# 1-Schematic_Task_10_1HD.net
KiCad netlist of a schematic drawn in EasyEDA
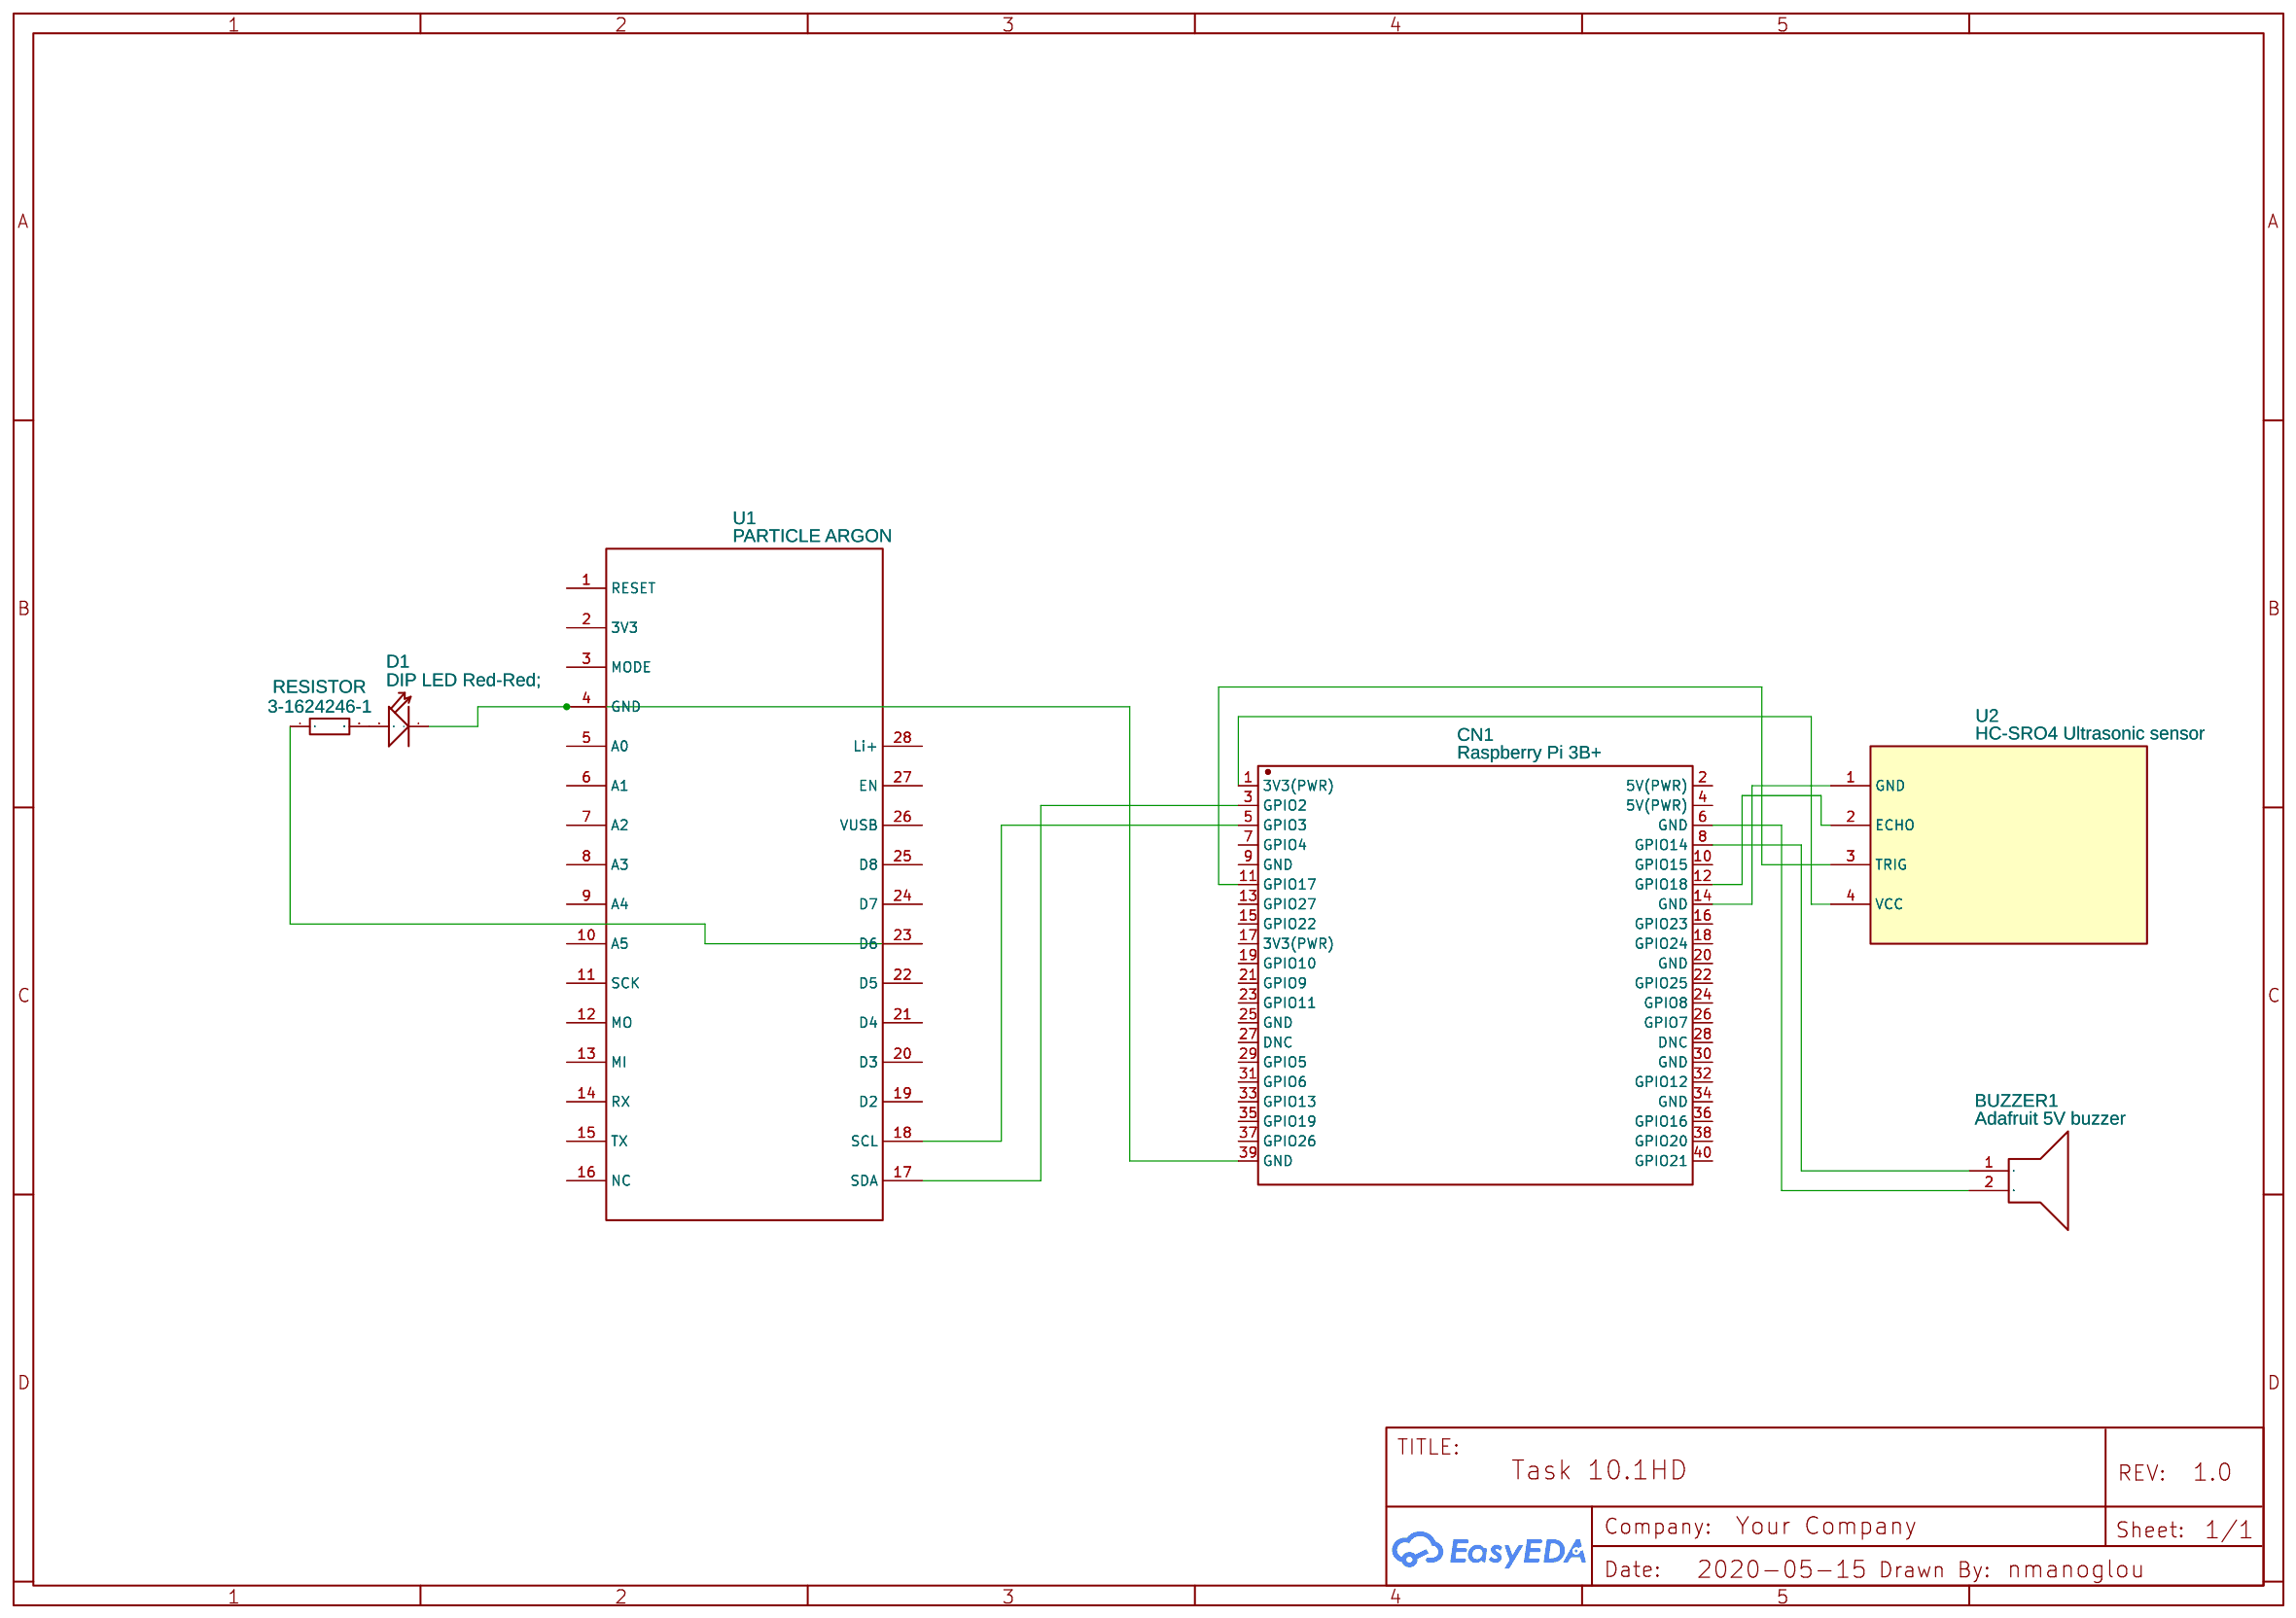
[diagram p0: schematic sheet]

(export (version "E")
  (design (tool "Eeschema 10.0.6"))
  (components
    (comp (ref "BUZZER1")
      (value "Adafruit 5V buzzer")
      (fields
        (field (name "BOM_Manufacturer Part") "GMC12085YA-16R2048")
        (field (name "BOM_Supplier Part") "C252920")
      )
      (libsource (lib "") (part "GMC12085YA-16R2048"))
    )
    (comp (ref "CN1") (value "Raspberry Pi 3B+") (libsource (lib "") (part "Raspberry Pi 2")))
    (comp (ref "D1")
      (value "DIP LED Red-Red;")
      (fields (field (name "BOM_Manufacturer Part") "?"))
      (libsource (lib "") (part "DIP LED Red-Red;"))
    )
    (comp (ref "RESISTOR")
      (value "3-1624246-1")
      (fields (field (name "BOM_Supplier Part") "C306238"))
      (libsource (lib "") (part "3-1624246-1"))
    )
    (comp (ref "U1") (value "PARTICLE ARGON") (libsource (lib "") (part "PARTICLE ARGON")))
    (comp (ref "U2")
      (value "HC-SRO4 Ultrasonic sensor")
      (libsource (lib "") (part "38 kHz modulated IR sensor"))
    )
  )
  (nets
    (net (code "1") (name "Net-(BUZZER1-Pad2)") (class "Default")
      (node (ref "BUZZER1") (pin "2") (pinfunction "2_2") (pintype "unspecified"))
      (node (ref "CN1") (pin "6") (pinfunction "GND_6") (pintype "passive"))
    )
    (net (code "2") (name "Net-(CN1-GPIO2)") (class "Default")
      (node (ref "CN1") (pin "3") (pinfunction "GPIO2_3") (pintype "bidirectional"))
      (node (ref "U1") (pin "17") (pinfunction "SDA_17") (pintype "unspecified"))
    )
    (net (code "3") (name "Net-(CN1-GPIO3)") (class "Default")
      (node (ref "CN1") (pin "5") (pinfunction "GPIO3_5") (pintype "bidirectional"))
      (node (ref "U1") (pin "18") (pinfunction "SCL_18") (pintype "unspecified"))
    )
    (net (code "4") (name "Net-(CN1-GPIO14)") (class "Default")
      (node (ref "BUZZER1") (pin "1") (pinfunction "1_1") (pintype "unspecified"))
      (node (ref "CN1") (pin "8") (pinfunction "GPIO14_8") (pintype "passive"))
    )
    (net (code "5") (name "Net-(CN1-GPIO17)") (class "Default")
      (node (ref "CN1") (pin "11") (pinfunction "GPIO17_11") (pintype "bidirectional"))
      (node (ref "U2") (pin "3") (pinfunction "TRIG_3") (pintype "unspecified"))
    )
    (net (code "6") (name "Net-(CN1-GPIO18)") (class "Default")
      (node (ref "CN1") (pin "12") (pinfunction "GPIO18_12") (pintype "bidirectional"))
      (node (ref "U2") (pin "2") (pinfunction "ECHO_2") (pintype "unspecified"))
    )
    (net (code "7") (name "Net-(D1-+)") (class "Default")
      (node (ref "D1") (pin "A") (pinfunction "+_A") (pintype "unspecified"))
      (node (ref "RESISTOR") (pin "2") (pinfunction "2_2") (pintype "unspecified"))
    )
    (net (code "8") (name "Net-(D1--)") (class "Default")
      (node (ref "CN1") (pin "39") (pinfunction "GND_39") (pintype "passive"))
      (node (ref "D1") (pin "K") (pinfunction "-_K") (pintype "unspecified"))
      (node (ref "U1") (pin "4") (pinfunction "GND_4") (pintype "unspecified"))
    )
    (net (code "9") (name "Net-(U1-D6)") (class "Default")
      (node (ref "RESISTOR") (pin "1") (pinfunction "1_1") (pintype "unspecified"))
      (node (ref "U1") (pin "23") (pinfunction "D6_23") (pintype "unspecified"))
    )
    (net (code "10") (name "Net-(U2-GND)") (class "Default")
      (node (ref "CN1") (pin "14") (pinfunction "GND_14") (pintype "passive"))
      (node (ref "U2") (pin "1") (pinfunction "GND_1") (pintype "unspecified"))
    )
    (net (code "11") (name "Net-(U2-VCC)") (class "Default")
      (node (ref "CN1") (pin "1") (pinfunction "3V3(PWR)_1") (pintype "passive"))
      (node (ref "U2") (pin "4") (pinfunction "VCC_4") (pintype "unspecified"))
    )
    (net (code "12") (name "unconnected-(CN1-3V3(PWR)-Pad17)") (class "Default")
      (node (ref "CN1") (pin "17") (pinfunction "3V3(PWR)_17") (pintype "passive"))
    )
    (net (code "13") (name "unconnected-(CN1-5V(PWR)-Pad2)") (class "Default")
      (node (ref "CN1") (pin "2") (pinfunction "5V(PWR)_2") (pintype "passive"))
    )
    (net (code "14") (name "unconnected-(CN1-5V(PWR)-Pad4)") (class "Default")
      (node (ref "CN1") (pin "4") (pinfunction "5V(PWR)_4") (pintype "passive"))
    )
    (net (code "15") (name "unconnected-(CN1-DNC-Pad27)") (class "Default")
      (node (ref "CN1") (pin "27") (pinfunction "DNC_27") (pintype "unspecified"))
    )
    (net (code "16") (name "unconnected-(CN1-DNC-Pad28)") (class "Default")
      (node (ref "CN1") (pin "28") (pinfunction "DNC_28") (pintype "unspecified"))
    )
    (net (code "17") (name "unconnected-(CN1-GND-Pad9)") (class "Default")
      (node (ref "CN1") (pin "9") (pinfunction "GND_9") (pintype "passive"))
    )
    (net (code "18") (name "unconnected-(CN1-GND-Pad20)") (class "Default")
      (node (ref "CN1") (pin "20") (pinfunction "GND_20") (pintype "passive"))
    )
    (net (code "19") (name "unconnected-(CN1-GND-Pad25)") (class "Default")
      (node (ref "CN1") (pin "25") (pinfunction "GND_25") (pintype "passive"))
    )
    (net (code "20") (name "unconnected-(CN1-GND-Pad30)") (class "Default")
      (node (ref "CN1") (pin "30") (pinfunction "GND_30") (pintype "passive"))
    )
    (net (code "21") (name "unconnected-(CN1-GND-Pad34)") (class "Default")
      (node (ref "CN1") (pin "34") (pinfunction "GND_34") (pintype "passive"))
    )
    (net (code "22") (name "unconnected-(CN1-GPIO4-Pad7)") (class "Default")
      (node (ref "CN1") (pin "7") (pinfunction "GPIO4_7") (pintype "bidirectional"))
    )
    (net (code "23") (name "unconnected-(CN1-GPIO5-Pad29)") (class "Default")
      (node (ref "CN1") (pin "29") (pinfunction "GPIO5_29") (pintype "bidirectional"))
    )
    (net (code "24") (name "unconnected-(CN1-GPIO6-Pad31)") (class "Default")
      (node (ref "CN1") (pin "31") (pinfunction "GPIO6_31") (pintype "bidirectional"))
    )
    (net (code "25") (name "unconnected-(CN1-GPIO7-Pad26)") (class "Default")
      (node (ref "CN1") (pin "26") (pinfunction "GPIO7_26") (pintype "bidirectional"))
    )
    (net (code "26") (name "unconnected-(CN1-GPIO8-Pad24)") (class "Default")
      (node (ref "CN1") (pin "24") (pinfunction "GPIO8_24") (pintype "bidirectional"))
    )
    (net (code "27") (name "unconnected-(CN1-GPIO9-Pad21)") (class "Default")
      (node (ref "CN1") (pin "21") (pinfunction "GPIO9_21") (pintype "bidirectional"))
    )
    (net (code "28") (name "unconnected-(CN1-GPIO10-Pad19)") (class "Default")
      (node (ref "CN1") (pin "19") (pinfunction "GPIO10_19") (pintype "bidirectional"))
    )
    (net (code "29") (name "unconnected-(CN1-GPIO11-Pad23)") (class "Default")
      (node (ref "CN1") (pin "23") (pinfunction "GPIO11_23") (pintype "bidirectional"))
    )
    (net (code "30") (name "unconnected-(CN1-GPIO12-Pad32)") (class "Default")
      (node (ref "CN1") (pin "32") (pinfunction "GPIO12_32") (pintype "bidirectional"))
    )
    (net (code "31") (name "unconnected-(CN1-GPIO13-Pad33)") (class "Default")
      (node (ref "CN1") (pin "33") (pinfunction "GPIO13_33") (pintype "bidirectional"))
    )
    (net (code "32") (name "unconnected-(CN1-GPIO15-Pad10)") (class "Default")
      (node (ref "CN1") (pin "10") (pinfunction "GPIO15_10") (pintype "bidirectional"))
    )
    (net (code "33") (name "unconnected-(CN1-GPIO16-Pad36)") (class "Default")
      (node (ref "CN1") (pin "36") (pinfunction "GPIO16_36") (pintype "bidirectional"))
    )
    (net (code "34") (name "unconnected-(CN1-GPIO19-Pad35)") (class "Default")
      (node (ref "CN1") (pin "35") (pinfunction "GPIO19_35") (pintype "bidirectional"))
    )
    (net (code "35") (name "unconnected-(CN1-GPIO20-Pad38)") (class "Default")
      (node (ref "CN1") (pin "38") (pinfunction "GPIO20_38") (pintype "bidirectional"))
    )
    (net (code "36") (name "unconnected-(CN1-GPIO21-Pad40)") (class "Default")
      (node (ref "CN1") (pin "40") (pinfunction "GPIO21_40") (pintype "bidirectional"))
    )
    (net (code "37") (name "unconnected-(CN1-GPIO22-Pad15)") (class "Default")
      (node (ref "CN1") (pin "15") (pinfunction "GPIO22_15") (pintype "output"))
    )
    (net (code "38") (name "unconnected-(CN1-GPIO23-Pad16)") (class "Default")
      (node (ref "CN1") (pin "16") (pinfunction "GPIO23_16") (pintype "bidirectional"))
    )
    (net (code "39") (name "unconnected-(CN1-GPIO24-Pad18)") (class "Default")
      (node (ref "CN1") (pin "18") (pinfunction "GPIO24_18") (pintype "bidirectional"))
    )
    (net (code "40") (name "unconnected-(CN1-GPIO25-Pad22)") (class "Default")
      (node (ref "CN1") (pin "22") (pinfunction "GPIO25_22") (pintype "bidirectional"))
    )
    (net (code "41") (name "unconnected-(CN1-GPIO26-Pad37)") (class "Default")
      (node (ref "CN1") (pin "37") (pinfunction "GPIO26_37") (pintype "bidirectional"))
    )
    (net (code "42") (name "unconnected-(CN1-GPIO27-Pad13)") (class "Default")
      (node (ref "CN1") (pin "13") (pinfunction "GPIO27_13") (pintype "bidirectional"))
    )
    (net (code "43") (name "unconnected-(U1-3V3-Pad2)") (class "Default")
      (node (ref "U1") (pin "2") (pinfunction "3V3_2") (pintype "unspecified"))
    )
    (net (code "44") (name "unconnected-(U1-A0-Pad5)") (class "Default")
      (node (ref "U1") (pin "5") (pinfunction "A0_5") (pintype "unspecified"))
    )
    (net (code "45") (name "unconnected-(U1-A1-Pad6)") (class "Default")
      (node (ref "U1") (pin "6") (pinfunction "A1_6") (pintype "unspecified"))
    )
    (net (code "46") (name "unconnected-(U1-A2-Pad7)") (class "Default")
      (node (ref "U1") (pin "7") (pinfunction "A2_7") (pintype "unspecified"))
    )
    (net (code "47") (name "unconnected-(U1-A3-Pad8)") (class "Default")
      (node (ref "U1") (pin "8") (pinfunction "A3_8") (pintype "unspecified"))
    )
    (net (code "48") (name "unconnected-(U1-A4-Pad9)") (class "Default")
      (node (ref "U1") (pin "9") (pinfunction "A4_9") (pintype "unspecified"))
    )
    (net (code "49") (name "unconnected-(U1-A5-Pad10)") (class "Default")
      (node (ref "U1") (pin "10") (pinfunction "A5_10") (pintype "unspecified"))
    )
    (net (code "50") (name "unconnected-(U1-D2-Pad19)") (class "Default")
      (node (ref "U1") (pin "19") (pinfunction "D2_19") (pintype "unspecified"))
    )
    (net (code "51") (name "unconnected-(U1-D3-Pad20)") (class "Default")
      (node (ref "U1") (pin "20") (pinfunction "D3_20") (pintype "unspecified"))
    )
    (net (code "52") (name "unconnected-(U1-D4-Pad21)") (class "Default")
      (node (ref "U1") (pin "21") (pinfunction "D4_21") (pintype "unspecified"))
    )
    (net (code "53") (name "unconnected-(U1-D5-Pad22)") (class "Default")
      (node (ref "U1") (pin "22") (pinfunction "D5_22") (pintype "unspecified"))
    )
    (net (code "54") (name "unconnected-(U1-D7-Pad24)") (class "Default")
      (node (ref "U1") (pin "24") (pinfunction "D7_24") (pintype "unspecified"))
    )
    (net (code "55") (name "unconnected-(U1-D8-Pad25)") (class "Default")
      (node (ref "U1") (pin "25") (pinfunction "D8_25") (pintype "unspecified"))
    )
    (net (code "56") (name "unconnected-(U1-EN-Pad27)") (class "Default")
      (node (ref "U1") (pin "27") (pinfunction "EN_27") (pintype "unspecified"))
    )
    (net (code "57") (name "unconnected-(U1-Li+-Pad28)") (class "Default")
      (node (ref "U1") (pin "28") (pinfunction "Li+_28") (pintype "unspecified"))
    )
    (net (code "58") (name "unconnected-(U1-MI-Pad13)") (class "Default")
      (node (ref "U1") (pin "13") (pinfunction "MI_13") (pintype "unspecified"))
    )
    (net (code "59") (name "unconnected-(U1-MO-Pad12)") (class "Default")
      (node (ref "U1") (pin "12") (pinfunction "MO_12") (pintype "unspecified"))
    )
    (net (code "60") (name "unconnected-(U1-MODE-Pad3)") (class "Default")
      (node (ref "U1") (pin "3") (pinfunction "MODE_3") (pintype "unspecified"))
    )
    (net (code "61") (name "unconnected-(U1-NC-Pad16)") (class "Default")
      (node (ref "U1") (pin "16") (pinfunction "NC_16") (pintype "unspecified"))
    )
    (net (code "62") (name "unconnected-(U1-RESET-Pad1)") (class "Default")
      (node (ref "U1") (pin "1") (pinfunction "RESET_1") (pintype "unspecified"))
    )
    (net (code "63") (name "unconnected-(U1-RX-Pad14)") (class "Default")
      (node (ref "U1") (pin "14") (pinfunction "RX_14") (pintype "unspecified"))
    )
    (net (code "64") (name "unconnected-(U1-SCK-Pad11)") (class "Default")
      (node (ref "U1") (pin "11") (pinfunction "SCK_11") (pintype "unspecified"))
    )
    (net (code "65") (name "unconnected-(U1-TX-Pad15)") (class "Default")
      (node (ref "U1") (pin "15") (pinfunction "TX_15") (pintype "unspecified"))
    )
    (net (code "66") (name "unconnected-(U1-VUSB-Pad26)") (class "Default")
      (node (ref "U1") (pin "26") (pinfunction "VUSB_26") (pintype "unspecified"))
    )
  )
)
